# ledDrive.net
KiCad netlist of a schematic drawn in Altium Designer
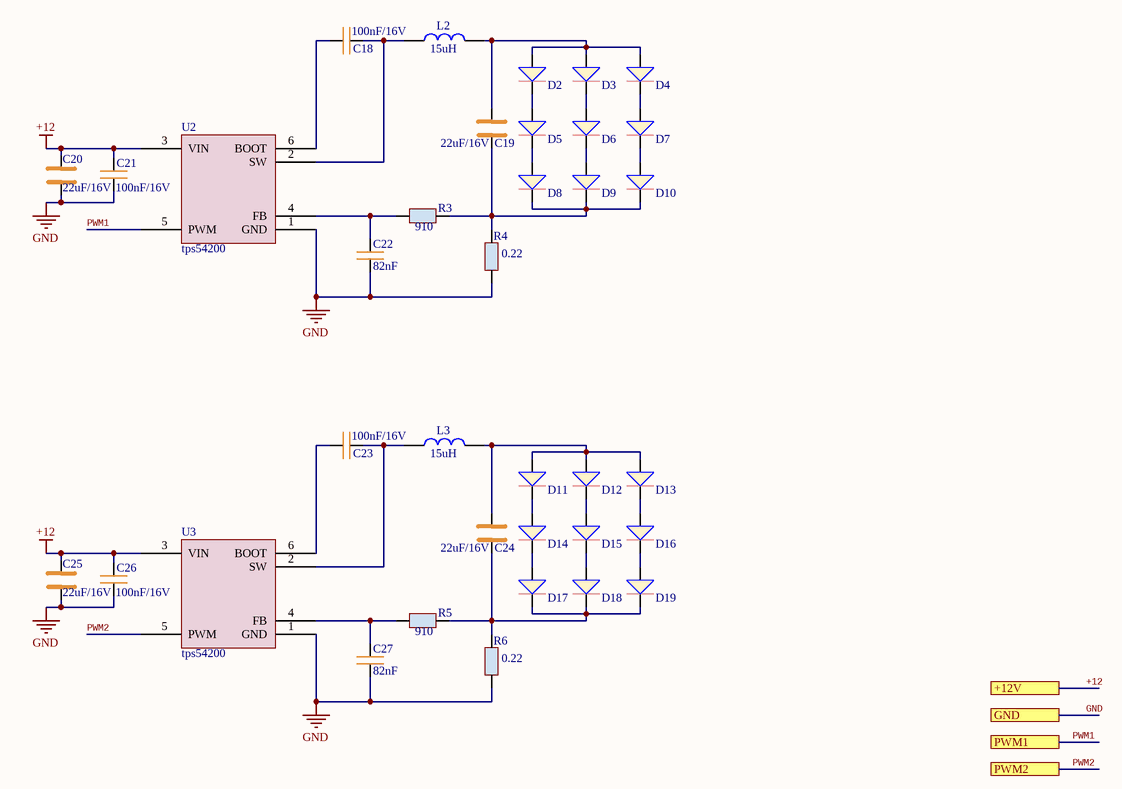
[diagram p0: ledDrive.SchDoc]

(export (version "E")
  (design (tool "Eeschema 10.0.6"))
  (components
    (comp (ref "C18")
      (value "100nF/16V")
      (footprint "CAP0603")
      (description "CAP0603")
      (libsource (lib "led2") (part "CAP0603"))
    )
    (comp (ref "C19")
      (value "22uF/16V")
      (footprint "cap1210")
      (description "CAP1210")
      (libsource (lib "led2") (part "CAP1210"))
    )
    (comp (ref "C20")
      (value "22uF/16V")
      (footprint "cap1210")
      (description "CAP1210")
      (libsource (lib "led2") (part "CAP1210"))
    )
    (comp (ref "C21")
      (value "100nF/16V")
      (footprint "CAP0603")
      (description "CAP0603")
      (libsource (lib "led2") (part "CAP0603"))
    )
    (comp (ref "C22")
      (value "82nF")
      (footprint "CAP0603")
      (description "CAP0603")
      (libsource (lib "led2") (part "CAP0603"))
    )
    (comp (ref "C23")
      (value "100nF/16V")
      (footprint "CAP0603")
      (description "CAP0603")
      (libsource (lib "led2") (part "CAP0603"))
    )
    (comp (ref "C24")
      (value "22uF/16V")
      (footprint "cap1210")
      (description "CAP1210")
      (libsource (lib "led2") (part "CAP1210"))
    )
    (comp (ref "C25")
      (value "22uF/16V")
      (footprint "cap1210")
      (description "CAP1210")
      (libsource (lib "led2") (part "CAP1210"))
    )
    (comp (ref "C26")
      (value "100nF/16V")
      (footprint "CAP0603")
      (description "CAP0603")
      (libsource (lib "led2") (part "CAP0603"))
    )
    (comp (ref "C27")
      (value "82nF")
      (footprint "CAP0603")
      (description "CAP0603")
      (libsource (lib "led2") (part "CAP0603"))
    )
    (comp (ref "D2")
      (value "LED3030")
      (footprint "LED3030")
      (description "LEd3030")
      (libsource (lib "led2") (part "LED3030"))
    )
    (comp (ref "D3")
      (value "LED3030")
      (footprint "LED3030")
      (description "LEd3030")
      (libsource (lib "led2") (part "LED3030"))
    )
    (comp (ref "D4")
      (value "LED3030")
      (footprint "LED3030")
      (description "LEd3030")
      (libsource (lib "led2") (part "LED3030"))
    )
    (comp (ref "D5")
      (value "LED3030")
      (footprint "LED3030")
      (description "LEd3030")
      (libsource (lib "led2") (part "LED3030"))
    )
    (comp (ref "D6")
      (value "LED3030")
      (footprint "LED3030")
      (description "LEd3030")
      (libsource (lib "led2") (part "LED3030"))
    )
    (comp (ref "D7")
      (value "LED3030")
      (footprint "LED3030")
      (description "LEd3030")
      (libsource (lib "led2") (part "LED3030"))
    )
    (comp (ref "D8")
      (value "LED3030")
      (footprint "LED3030")
      (description "LEd3030")
      (libsource (lib "led2") (part "LED3030"))
    )
    (comp (ref "D9")
      (value "LED3030")
      (footprint "LED3030")
      (description "LEd3030")
      (libsource (lib "led2") (part "LED3030"))
    )
    (comp (ref "D10")
      (value "LED3030")
      (footprint "LED3030")
      (description "LEd3030")
      (libsource (lib "led2") (part "LED3030"))
    )
    (comp (ref "D11")
      (value "LED3030")
      (footprint "LED3030")
      (description "LEd3030")
      (libsource (lib "led2") (part "LED3030"))
    )
    (comp (ref "D12")
      (value "LED3030")
      (footprint "LED3030")
      (description "LEd3030")
      (libsource (lib "led2") (part "LED3030"))
    )
    (comp (ref "D13")
      (value "LED3030")
      (footprint "LED3030")
      (description "LEd3030")
      (libsource (lib "led2") (part "LED3030"))
    )
    (comp (ref "D14")
      (value "LED3030")
      (footprint "LED3030")
      (description "LEd3030")
      (libsource (lib "led2") (part "LED3030"))
    )
    (comp (ref "D15")
      (value "LED3030")
      (footprint "LED3030")
      (description "LEd3030")
      (libsource (lib "led2") (part "LED3030"))
    )
    (comp (ref "D16")
      (value "LED3030")
      (footprint "LED3030")
      (description "LEd3030")
      (libsource (lib "led2") (part "LED3030"))
    )
    (comp (ref "D17")
      (value "LED3030")
      (footprint "LED3030")
      (description "LEd3030")
      (libsource (lib "led2") (part "LED3030"))
    )
    (comp (ref "D18")
      (value "LED3030")
      (footprint "LED3030")
      (description "LEd3030")
      (libsource (lib "led2") (part "LED3030"))
    )
    (comp (ref "D19")
      (value "LED3030")
      (footprint "LED3030")
      (description "LEd3030")
      (libsource (lib "led2") (part "LED3030"))
    )
    (comp (ref "L2")
      (value "15uH")
      (footprint "Inductor7x7")
      (description "a ind")
      (libsource (lib "led2") (part "ind7x7"))
    )
    (comp (ref "L3")
      (value "15uH")
      (footprint "Inductor7x7")
      (description "a ind")
      (libsource (lib "led2") (part "ind7x7"))
    )
    (comp (ref "R3")
      (value "910")
      (footprint "res0603")
      (description "RES0603")
      (libsource (lib "led2") (part "RES0603"))
    )
    (comp (ref "R4")
      (value "0.22")
      (footprint "res1206")
      (description "RES1206")
      (libsource (lib "led2") (part "RES1206"))
    )
    (comp (ref "R5")
      (value "910")
      (footprint "res0603")
      (description "RES0603")
      (libsource (lib "led2") (part "RES0603"))
    )
    (comp (ref "R6")
      (value "0.22")
      (footprint "res1206")
      (description "RES1206")
      (libsource (lib "led2") (part "RES1206"))
    )
    (comp (ref "U2") (value "tps54200") (footprint "TPS54200") (libsource (lib "led2") (part "tps54200")))
    (comp (ref "U3") (value "tps54200") (footprint "TPS54200") (libsource (lib "led2") (part "tps54200")))
  )
  (nets
    (net (code "1") (name "+12") (class "Default")
      (node (ref "C20") (pin "2") (pintype "passive"))
      (node (ref "C21") (pin "2") (pintype "passive"))
      (node (ref "C25") (pin "2") (pintype "passive"))
      (node (ref "C26") (pin "2") (pintype "passive"))
      (node (ref "U2") (pin "3") (pinfunction "VIN_3") (pintype "passive"))
      (node (ref "U3") (pin "3") (pinfunction "VIN_3") (pintype "passive"))
    )
    (net (code "2") (name "/PWM1") (class "Default")
      (node (ref "U2") (pin "5") (pinfunction "PWM_5") (pintype "passive"))
    )
    (net (code "3") (name "/PWM2") (class "Default")
      (node (ref "U3") (pin "5") (pinfunction "PWM_5") (pintype "passive"))
    )
    (net (code "4") (name "GND") (class "Default")
      (node (ref "C20") (pin "1") (pintype "passive"))
      (node (ref "C21") (pin "1") (pintype "passive"))
      (node (ref "C22") (pin "2") (pintype "passive"))
      (node (ref "C25") (pin "1") (pintype "passive"))
      (node (ref "C26") (pin "1") (pintype "passive"))
      (node (ref "C27") (pin "2") (pintype "passive"))
      (node (ref "R4") (pin "1") (pintype "passive"))
      (node (ref "R6") (pin "1") (pintype "passive"))
      (node (ref "U2") (pin "1") (pinfunction "GND_1") (pintype "passive"))
      (node (ref "U3") (pin "1") (pinfunction "GND_1") (pintype "passive"))
    )
    (net (code "5") (name "Net-(C19-Pad1)") (class "Default")
      (node (ref "C19") (pin "1") (pintype "passive"))
      (node (ref "D10") (pin "1") (pintype "passive"))
      (node (ref "D8") (pin "1") (pintype "passive"))
      (node (ref "D9") (pin "1") (pintype "passive"))
      (node (ref "R3") (pin "2") (pintype "passive"))
      (node (ref "R4") (pin "2") (pintype "passive"))
    )
    (net (code "6") (name "Net-(C19-Pad2)") (class "Default")
      (node (ref "C19") (pin "2") (pintype "passive"))
      (node (ref "D2") (pin "2") (pintype "passive"))
      (node (ref "D3") (pin "2") (pintype "passive"))
      (node (ref "D4") (pin "2") (pintype "passive"))
      (node (ref "L2") (pin "2") (pintype "passive"))
    )
    (net (code "7") (name "Net-(C24-Pad1)") (class "Default")
      (node (ref "C24") (pin "1") (pintype "passive"))
      (node (ref "D17") (pin "1") (pintype "passive"))
      (node (ref "D18") (pin "1") (pintype "passive"))
      (node (ref "D19") (pin "1") (pintype "passive"))
      (node (ref "R5") (pin "2") (pintype "passive"))
      (node (ref "R6") (pin "2") (pintype "passive"))
    )
    (net (code "8") (name "Net-(C24-Pad2)") (class "Default")
      (node (ref "C24") (pin "2") (pintype "passive"))
      (node (ref "D11") (pin "2") (pintype "passive"))
      (node (ref "D12") (pin "2") (pintype "passive"))
      (node (ref "D13") (pin "2") (pintype "passive"))
      (node (ref "L3") (pin "2") (pintype "passive"))
    )
    (net (code "9") (name "Net-(D2-Pad1)") (class "Default")
      (node (ref "D2") (pin "1") (pintype "passive"))
      (node (ref "D5") (pin "2") (pintype "passive"))
    )
    (net (code "10") (name "Net-(D3-Pad1)") (class "Default")
      (node (ref "D3") (pin "1") (pintype "passive"))
      (node (ref "D6") (pin "2") (pintype "passive"))
    )
    (net (code "11") (name "Net-(D4-Pad1)") (class "Default")
      (node (ref "D4") (pin "1") (pintype "passive"))
      (node (ref "D7") (pin "2") (pintype "passive"))
    )
    (net (code "12") (name "Net-(D5-Pad1)") (class "Default")
      (node (ref "D5") (pin "1") (pintype "passive"))
      (node (ref "D8") (pin "2") (pintype "passive"))
    )
    (net (code "13") (name "Net-(D6-Pad1)") (class "Default")
      (node (ref "D6") (pin "1") (pintype "passive"))
      (node (ref "D9") (pin "2") (pintype "passive"))
    )
    (net (code "14") (name "Net-(D10-Pad2)") (class "Default")
      (node (ref "D10") (pin "2") (pintype "passive"))
      (node (ref "D7") (pin "1") (pintype "passive"))
    )
    (net (code "15") (name "Net-(D11-Pad1)") (class "Default")
      (node (ref "D11") (pin "1") (pintype "passive"))
      (node (ref "D14") (pin "2") (pintype "passive"))
    )
    (net (code "16") (name "Net-(D12-Pad1)") (class "Default")
      (node (ref "D12") (pin "1") (pintype "passive"))
      (node (ref "D15") (pin "2") (pintype "passive"))
    )
    (net (code "17") (name "Net-(D13-Pad1)") (class "Default")
      (node (ref "D13") (pin "1") (pintype "passive"))
      (node (ref "D16") (pin "2") (pintype "passive"))
    )
    (net (code "18") (name "Net-(D14-Pad1)") (class "Default")
      (node (ref "D14") (pin "1") (pintype "passive"))
      (node (ref "D17") (pin "2") (pintype "passive"))
    )
    (net (code "19") (name "Net-(D15-Pad1)") (class "Default")
      (node (ref "D15") (pin "1") (pintype "passive"))
      (node (ref "D18") (pin "2") (pintype "passive"))
    )
    (net (code "20") (name "Net-(D16-Pad1)") (class "Default")
      (node (ref "D16") (pin "1") (pintype "passive"))
      (node (ref "D19") (pin "2") (pintype "passive"))
    )
    (net (code "21") (name "Net-(U2-BOOT)") (class "Default")
      (node (ref "C18") (pin "2") (pintype "passive"))
      (node (ref "U2") (pin "6") (pinfunction "BOOT_6") (pintype "passive"))
    )
    (net (code "22") (name "Net-(U2-FB)") (class "Default")
      (node (ref "C22") (pin "1") (pintype "passive"))
      (node (ref "R3") (pin "1") (pintype "passive"))
      (node (ref "U2") (pin "4") (pinfunction "FB_4") (pintype "passive"))
    )
    (net (code "23") (name "Net-(U2-SW)") (class "Default")
      (node (ref "C18") (pin "1") (pintype "passive"))
      (node (ref "L2") (pin "1") (pintype "passive"))
      (node (ref "U2") (pin "2") (pinfunction "SW_2") (pintype "passive"))
    )
    (net (code "24") (name "Net-(U3-BOOT)") (class "Default")
      (node (ref "C23") (pin "2") (pintype "passive"))
      (node (ref "U3") (pin "6") (pinfunction "BOOT_6") (pintype "passive"))
    )
    (net (code "25") (name "Net-(U3-FB)") (class "Default")
      (node (ref "C27") (pin "1") (pintype "passive"))
      (node (ref "R5") (pin "1") (pintype "passive"))
      (node (ref "U3") (pin "4") (pinfunction "FB_4") (pintype "passive"))
    )
    (net (code "26") (name "Net-(U3-SW)") (class "Default")
      (node (ref "C23") (pin "1") (pintype "passive"))
      (node (ref "L3") (pin "1") (pintype "passive"))
      (node (ref "U3") (pin "2") (pinfunction "SW_2") (pintype "passive"))
    )
  )
)
